# power_on_board.net
KiCad netlist of a schematic drawn in EAGLE
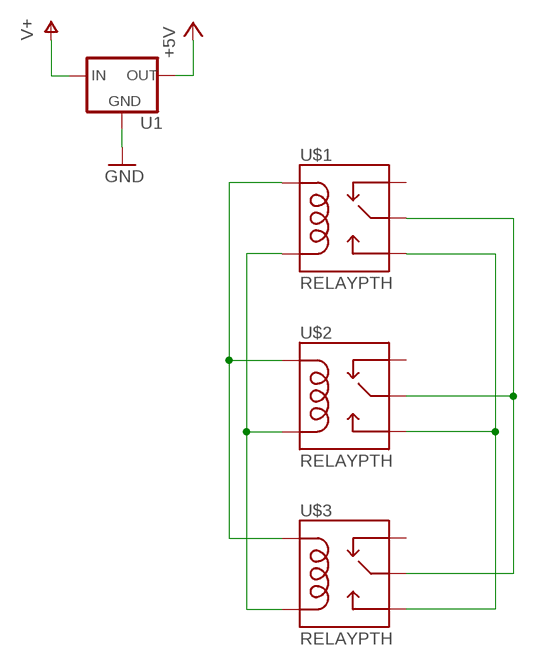
[diagram p0: schematic, sheet 1]

(export (version "E")
  (design (tool "Eeschema 10.0.6"))
  (components
    (comp (ref "U$1")
      (value "RELAYPTH")
      (footprint "eagle-import:SRD-05VDC-SL-C")
      (libsource (lib "eagle-import") (part "RELAYPTH"))
    )
    (comp (ref "U$2")
      (value "RELAYPTH")
      (footprint "eagle-import:SRD-05VDC-SL-C")
      (libsource (lib "eagle-import") (part "RELAYPTH"))
    )
    (comp (ref "U$3")
      (value "RELAYPTH")
      (footprint "eagle-import:SRD-05VDC-SL-C")
      (libsource (lib "eagle-import") (part "RELAYPTH"))
    )
    (comp (ref "U1")
      (value "V_REG_78XX-TO-220")
      (footprint "eagle-import:TO-220-ALT")
      (libsource (lib "eagle-import") (part "V_REG_78XX-TO-220"))
    )
  )
  (nets
    (net (code "1") (name "+5V") (class "Default")
      (node (ref "U1") (pin "OUT") (pinfunction "OUT_OUT") (pintype "passive"))
    )
    (net (code "2") (name "GND") (class "Default")
      (node (ref "U1") (pin "GND") (pinfunction "GND_GND") (pintype "input"))
    )
    (net (code "3") (name "Net-(U$1-PadCOIL0)") (class "Default")
      (node (ref "U$1") (pin "COIL0") (pinfunction "COIL0_COIL0") (pintype "bidirectional"))
      (node (ref "U$2") (pin "COIL0") (pinfunction "COIL0_COIL0") (pintype "bidirectional"))
      (node (ref "U$3") (pin "COIL0") (pinfunction "COIL0_COIL0") (pintype "bidirectional"))
    )
    (net (code "4") (name "Net-(U$1-PadCOIL1)") (class "Default")
      (node (ref "U$1") (pin "COIL1") (pinfunction "COIL1_COIL1") (pintype "bidirectional"))
      (node (ref "U$2") (pin "COIL1") (pinfunction "COIL1_COIL1") (pintype "bidirectional"))
      (node (ref "U$3") (pin "COIL1") (pinfunction "COIL1_COIL1") (pintype "bidirectional"))
    )
    (net (code "5") (name "Net-(U$1-PadSWCOMMON)") (class "Default")
      (node (ref "U$1") (pin "SWCOMMON") (pinfunction "SWCOMMON_SWCOMMON") (pintype "bidirectional"))
      (node (ref "U$2") (pin "SWCOMMON") (pinfunction "SWCOMMON_SWCOMMON") (pintype "bidirectional"))
      (node (ref "U$3") (pin "SWCOMMON") (pinfunction "SWCOMMON_SWCOMMON") (pintype "bidirectional"))
    )
    (net (code "6") (name "Net-(U$1-PadSWOPEN)") (class "Default")
      (node (ref "U$1") (pin "SWOPEN") (pinfunction "SWOPEN_SWOPEN") (pintype "bidirectional"))
      (node (ref "U$2") (pin "SWOPEN") (pinfunction "SWOPEN_SWOPEN") (pintype "bidirectional"))
      (node (ref "U$3") (pin "SWOPEN") (pinfunction "SWOPEN_SWOPEN") (pintype "bidirectional"))
    )
    (net (code "7") (name "V+") (class "Default")
      (node (ref "U1") (pin "IN") (pinfunction "IN_IN") (pintype "input"))
    )
    (net (code "8") (name "unconnected-(U$1-SWCLOSE-PadSWCLOSED)") (class "Default")
      (node (ref "U$1") (pin "SWCLOSED") (pinfunction "SWCLOSE_SWCLOSED") (pintype "bidirectional"))
    )
    (net (code "9") (name "unconnected-(U$2-SWCLOSE-PadSWCLOSED)") (class "Default")
      (node (ref "U$2") (pin "SWCLOSED") (pinfunction "SWCLOSE_SWCLOSED") (pintype "bidirectional"))
    )
    (net (code "10") (name "unconnected-(U$3-SWCLOSE-PadSWCLOSED)") (class "Default")
      (node (ref "U$3") (pin "SWCLOSED") (pinfunction "SWCLOSE_SWCLOSED") (pintype "bidirectional"))
    )
  )
)
